# mp28164-buck-boost-flashlight-driver-tes.net
KiCad netlist of a schematic drawn in EAGLE
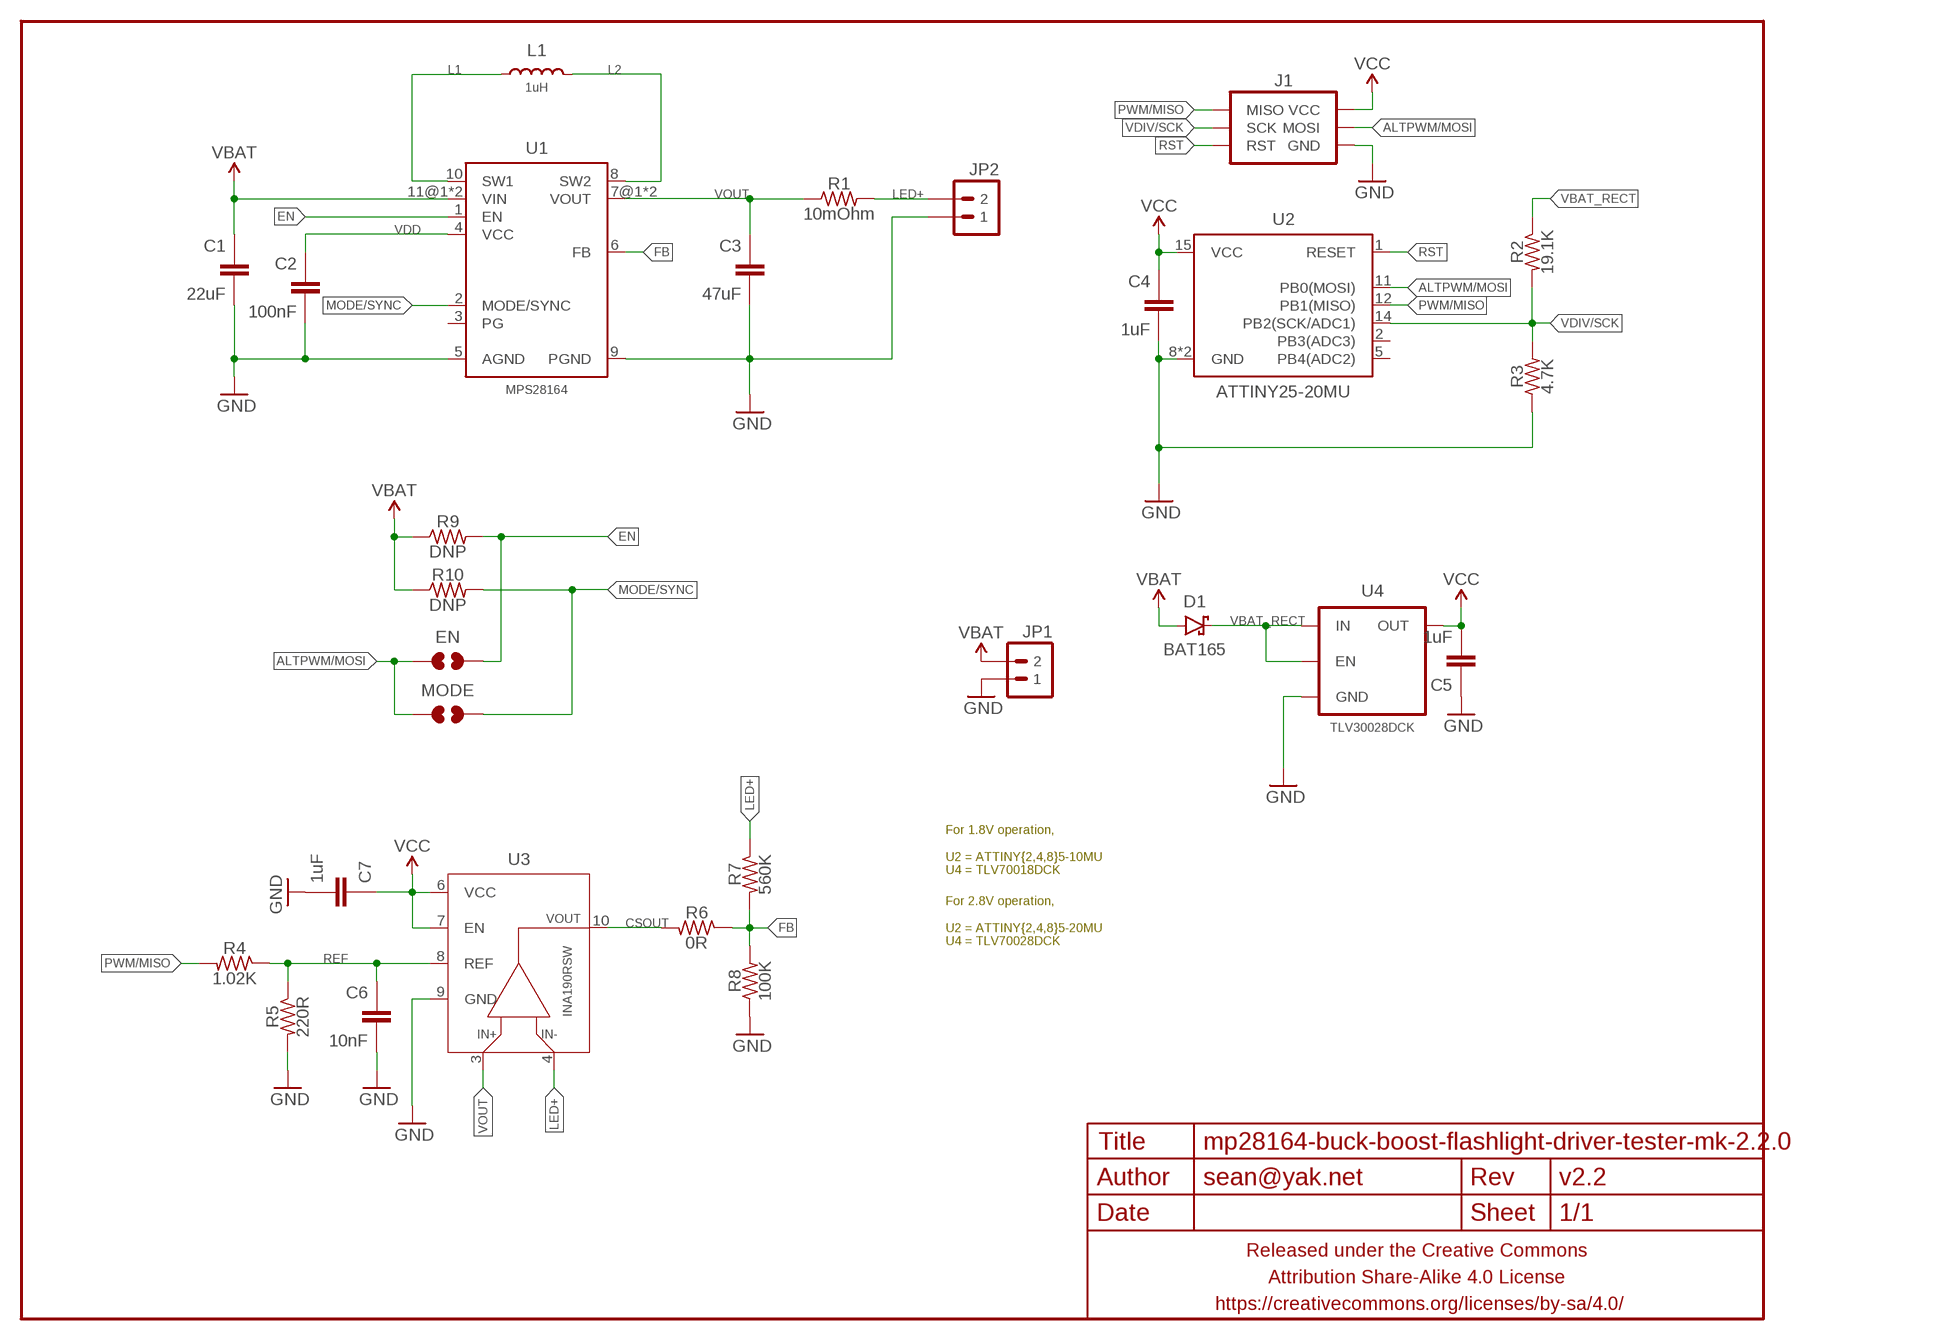
[diagram p0: schematic, sheet 1]

(export (version "E")
  (design (tool "Eeschema 10.0.6"))
  (components
    (comp (ref "C1")
      (value "22uF")
      (footprint "eagle-import:C1206")
      (libsource (lib "eagle-import") (part "CAPACITOR-CERAMICC1206"))
    )
    (comp (ref "C2")
      (value "100nF")
      (footprint "eagle-import:C0402")
      (libsource (lib "eagle-import") (part "CAPACITOR-CERAMICC0402"))
    )
    (comp (ref "C3")
      (value "47uF")
      (footprint "eagle-import:C1206")
      (libsource (lib "eagle-import") (part "CAPACITOR-CERAMICC1206"))
    )
    (comp (ref "C4")
      (value "1uF")
      (footprint "eagle-import:C0402")
      (libsource (lib "eagle-import") (part "CAPACITOR-CERAMICC0402"))
    )
    (comp (ref "C5")
      (value "1uF")
      (footprint "eagle-import:C0402")
      (libsource (lib "eagle-import") (part "CAPACITOR-CERAMICC0402"))
    )
    (comp (ref "C6")
      (value "10nF")
      (footprint "eagle-import:C0402")
      (libsource (lib "eagle-import") (part "CAPACITOR-CERAMICC0402"))
    )
    (comp (ref "C7")
      (value "1uF")
      (footprint "eagle-import:C0402")
      (libsource (lib "eagle-import") (part "CAPACITOR-CERAMICC0402"))
    )
    (comp (ref "D1")
      (value "BAT165")
      (footprint "eagle-import:SOD323-SCHOTTKY")
      (libsource (lib "eagle-import") (part "DIODE-SCHOTTKYSOD323"))
    )
    (comp (ref "EN")
      (value "JUMPER-PAD-2-NOYES_SILK")
      (footprint "eagle-import:PAD-JUMPER-2-NO_YES_SILK")
      (libsource (lib "eagle-import") (part "JUMPER-PAD-2-NOYES_SILK"))
    )
    (comp (ref "FRAME1")
      (value "FRAME-LETTERNO_PACKAGE")
      (footprint "eagle-import:DUMMY")
      (fields
        (field (name "DESIGNER") "sean@yak.net")
        (field (name "VERSION") "v2.2")
        (field (name "DESIGNER_1") "sean@yak.net")
        (field (name "VERSION_1") "v2.2")
      )
      (libsource (lib "eagle-import") (part "FRAME-LETTERNO_PACKAGE"))
    )
    (comp (ref "J1")
      (value "AVR_SPI_PRG_6PTH")
      (footprint "eagle-import:2X3")
      (libsource (lib "eagle-import") (part "AVR_SPI_PRG_6PTH"))
    )
    (comp (ref "JP1")
      (value "M021X02_NO_SILK")
      (footprint "eagle-import:1X02_NO_SILK")
      (libsource (lib "eagle-import") (part "M021X02_NO_SILK"))
    )
    (comp (ref "JP2")
      (value "M021X02_NO_SILK")
      (footprint "eagle-import:1X02_NO_SILK")
      (libsource (lib "eagle-import") (part "M021X02_NO_SILK"))
    )
    (comp (ref "L1")
      (value "1uH")
      (footprint "eagle-import:XAL60XX")
      (libsource (lib "eagle-import") (part "INDUCTORXAL60XX"))
    )
    (comp (ref "MODE")
      (value "JUMPER-PAD-2-NOYES_SILK")
      (footprint "eagle-import:PAD-JUMPER-2-NO_YES_SILK")
      (libsource (lib "eagle-import") (part "JUMPER-PAD-2-NOYES_SILK"))
    )
    (comp (ref "R1")
      (value "10mOhm")
      (footprint "eagle-import:R1206")
      (libsource (lib "eagle-import") (part "RESISTORR1206"))
    )
    (comp (ref "R2")
      (value "19.1K")
      (footprint "eagle-import:R0402")
      (libsource (lib "eagle-import") (part "RESISTORR0402"))
    )
    (comp (ref "R3")
      (value "4.7K")
      (footprint "eagle-import:R0402")
      (libsource (lib "eagle-import") (part "RESISTORR0402"))
    )
    (comp (ref "R4")
      (value "1.02K")
      (footprint "eagle-import:R0402")
      (libsource (lib "eagle-import") (part "RESISTORR0402"))
    )
    (comp (ref "R5")
      (value "220R")
      (footprint "eagle-import:R0402")
      (libsource (lib "eagle-import") (part "RESISTORR0402"))
    )
    (comp (ref "R6")
      (value "0R")
      (footprint "eagle-import:R0402")
      (libsource (lib "eagle-import") (part "RESISTORR0402"))
    )
    (comp (ref "R7")
      (value "560K")
      (footprint "eagle-import:R0402")
      (libsource (lib "eagle-import") (part "RESISTORR0402"))
    )
    (comp (ref "R8")
      (value "100K")
      (footprint "eagle-import:R0402")
      (libsource (lib "eagle-import") (part "RESISTORR0402"))
    )
    (comp (ref "R9")
      (value "DNP")
      (footprint "eagle-import:R0402")
      (libsource (lib "eagle-import") (part "RESISTORR0402"))
    )
    (comp (ref "R10")
      (value "DNP")
      (footprint "eagle-import:R0402")
      (libsource (lib "eagle-import") (part "RESISTORR0402"))
    )
    (comp (ref "U1")
      (value "MPS28164")
      (footprint "eagle-import:MPS28164")
      (libsource (lib "eagle-import") (part "MPS28164"))
    )
    (comp (ref "U2")
      (value "ATTINY25-20MU")
      (footprint "eagle-import:QFN20")
      (libsource (lib "eagle-import") (part "ATTINY45TINY85-20-QFN"))
    )
    (comp (ref "U3")
      (value "INA190RSW")
      (footprint "eagle-import:UQFN-10")
      (libsource (lib "eagle-import") (part "INA190RSW"))
    )
    (comp (ref "U4")
      (value "TLV30028DCK")
      (footprint "eagle-import:SC70-TIGHTER")
      (libsource (lib "eagle-import") (part "V_REG_ENTLV700XXDCK-TIGHTER"))
    )
  )
  (nets
    (net (code "1") (name "/CSOUT") (class "Default")
      (node (ref "R6") (pin "2") (pinfunction "2_2") (pintype "passive"))
      (node (ref "U3") (pin "10") (pinfunction "OUT_10") (pintype "bidirectional"))
    )
    (net (code "2") (name "/L1") (class "Default")
      (node (ref "L1") (pin "P$1") (pinfunction "1_P$1") (pintype "passive"))
      (node (ref "U1") (pin "10") (pinfunction "SW1_10") (pintype "bidirectional"))
    )
    (net (code "3") (name "/L2") (class "Default")
      (node (ref "L1") (pin "P$2") (pinfunction "2_P$2") (pintype "passive"))
      (node (ref "U1") (pin "8") (pinfunction "SW2_8") (pintype "bidirectional"))
    )
    (net (code "4") (name "/REF") (class "Default")
      (node (ref "C6") (pin "1") (pinfunction "1_1") (pintype "passive"))
      (node (ref "R4") (pin "1") (pinfunction "1_1") (pintype "passive"))
      (node (ref "R5") (pin "1") (pinfunction "1_1") (pintype "passive"))
      (node (ref "U3") (pin "8") (pinfunction "REF_8") (pintype "bidirectional"))
    )
    (net (code "5") (name "/VDD") (class "Default")
      (node (ref "C2") (pin "1") (pinfunction "1_1") (pintype "passive"))
      (node (ref "U1") (pin "4") (pinfunction "VCC_4") (pintype "bidirectional"))
    )
    (net (code "6") (name "ALTPWM{slash}MOSI") (class "Default")
      (node (ref "EN") (pin "1") (pinfunction "1_1") (pintype "passive"))
      (node (ref "J1") (pin "4") (pinfunction "MOSI_4") (pintype "passive"))
      (node (ref "MODE") (pin "1") (pinfunction "1_1") (pintype "passive"))
      (node (ref "U2") (pin "11") (pinfunction "PB0(MOSI)_11") (pintype "bidirectional"))
    )
    (net (code "7") (name "EN") (class "Default")
      (node (ref "EN") (pin "2") (pinfunction "2_2") (pintype "passive"))
      (node (ref "R9") (pin "2") (pinfunction "2_2") (pintype "passive"))
      (node (ref "U1") (pin "1") (pinfunction "EN_1") (pintype "bidirectional"))
    )
    (net (code "8") (name "FB") (class "Default")
      (node (ref "R6") (pin "1") (pinfunction "1_1") (pintype "passive"))
      (node (ref "R7") (pin "2") (pinfunction "2_2") (pintype "passive"))
      (node (ref "R8") (pin "2") (pinfunction "2_2") (pintype "passive"))
      (node (ref "U1") (pin "6") (pinfunction "FB_6") (pintype "bidirectional"))
    )
    (net (code "9") (name "GND") (class "Default")
      (node (ref "C1") (pin "2") (pinfunction "2_2") (pintype "passive"))
      (node (ref "C2") (pin "2") (pinfunction "2_2") (pintype "passive"))
      (node (ref "C3") (pin "2") (pinfunction "2_2") (pintype "passive"))
      (node (ref "C4") (pin "2") (pinfunction "2_2") (pintype "passive"))
      (node (ref "C5") (pin "1") (pinfunction "1_1") (pintype "passive"))
      (node (ref "C6") (pin "2") (pinfunction "2_2") (pintype "passive"))
      (node (ref "C7") (pin "2") (pinfunction "2_2") (pintype "passive"))
      (node (ref "J1") (pin "6") (pinfunction "GND_6") (pintype "passive"))
      (node (ref "JP1") (pin "1") (pinfunction "1_1") (pintype "passive"))
      (node (ref "JP2") (pin "1") (pinfunction "1_1") (pintype "passive"))
      (node (ref "R3") (pin "1") (pinfunction "1_1") (pintype "passive"))
      (node (ref "R5") (pin "2") (pinfunction "2_2") (pintype "passive"))
      (node (ref "R8") (pin "1") (pinfunction "1_1") (pintype "passive"))
      (node (ref "U1") (pin "5") (pinfunction "AGND_5") (pintype "bidirectional"))
      (node (ref "U1") (pin "9") (pinfunction "PGND_9") (pintype "bidirectional"))
      (node (ref "U2") (pin "8") (pinfunction "GND_8") (pintype "bidirectional"))
      (node (ref "U2") (pin "PAD") (pinfunction "GND_PAD") (pintype "bidirectional"))
      (node (ref "U3") (pin "9") (pinfunction "GND_9") (pintype "bidirectional"))
      (node (ref "U4") (pin "2") (pinfunction "GND_2") (pintype "input"))
    )
    (net (code "10") (name "LED+") (class "Default")
      (node (ref "JP2") (pin "2") (pinfunction "2_2") (pintype "passive"))
      (node (ref "R1") (pin "2") (pinfunction "2_2") (pintype "passive"))
      (node (ref "R7") (pin "1") (pinfunction "1_1") (pintype "passive"))
      (node (ref "U3") (pin "4") (pinfunction "VIN-_4") (pintype "bidirectional"))
    )
    (net (code "11") (name "MODE{slash}SYNC") (class "Default")
      (node (ref "MODE") (pin "2") (pinfunction "2_2") (pintype "passive"))
      (node (ref "R10") (pin "2") (pinfunction "2_2") (pintype "passive"))
      (node (ref "U1") (pin "2") (pinfunction "MODE/SYNC_2") (pintype "bidirectional"))
    )
    (net (code "12") (name "PWM{slash}MISO") (class "Default")
      (node (ref "J1") (pin "1") (pinfunction "MISO_1") (pintype "passive"))
      (node (ref "R4") (pin "2") (pinfunction "2_2") (pintype "passive"))
      (node (ref "U2") (pin "12") (pinfunction "PB1(MISO)_12") (pintype "bidirectional"))
    )
    (net (code "13") (name "RST") (class "Default")
      (node (ref "J1") (pin "5") (pinfunction "RST_5") (pintype "passive"))
      (node (ref "U2") (pin "1") (pinfunction "RESET_1") (pintype "bidirectional"))
    )
    (net (code "14") (name "VBAT") (class "Default")
      (node (ref "C1") (pin "1") (pinfunction "1_1") (pintype "passive"))
      (node (ref "D1") (pin "A") (pinfunction "A_A") (pintype "passive"))
      (node (ref "JP1") (pin "2") (pinfunction "2_2") (pintype "passive"))
      (node (ref "R10") (pin "1") (pinfunction "1_1") (pintype "passive"))
      (node (ref "R9") (pin "1") (pinfunction "1_1") (pintype "passive"))
      (node (ref "U1") (pin "11@1") (pinfunction "VIN_11@1") (pintype "bidirectional"))
      (node (ref "U1") (pin "11@2") (pinfunction "VIN_11@2") (pintype "bidirectional"))
    )
    (net (code "15") (name "VBAT_RECT") (class "Default")
      (node (ref "D1") (pin "C") (pinfunction "C_C") (pintype "passive"))
      (node (ref "R2") (pin "1") (pinfunction "1_1") (pintype "passive"))
      (node (ref "U4") (pin "1") (pinfunction "IN_1") (pintype "input"))
      (node (ref "U4") (pin "3") (pinfunction "EN_3") (pintype "input"))
    )
    (net (code "16") (name "VCC") (class "Default")
      (node (ref "C4") (pin "1") (pinfunction "1_1") (pintype "passive"))
      (node (ref "C5") (pin "2") (pinfunction "2_2") (pintype "passive"))
      (node (ref "C7") (pin "1") (pinfunction "1_1") (pintype "passive"))
      (node (ref "J1") (pin "2") (pinfunction "VCC_2") (pintype "passive"))
      (node (ref "U2") (pin "15") (pinfunction "VCC_15") (pintype "bidirectional"))
      (node (ref "U3") (pin "6") (pinfunction "VCC_6") (pintype "bidirectional"))
      (node (ref "U3") (pin "7") (pinfunction "EN_7") (pintype "bidirectional"))
      (node (ref "U4") (pin "5") (pinfunction "OUT_5") (pintype "passive"))
    )
    (net (code "17") (name "VDIV{slash}SCK") (class "Default")
      (node (ref "J1") (pin "3") (pinfunction "SCK_3") (pintype "passive"))
      (node (ref "R2") (pin "2") (pinfunction "2_2") (pintype "passive"))
      (node (ref "R3") (pin "2") (pinfunction "2_2") (pintype "passive"))
      (node (ref "U2") (pin "14") (pinfunction "PB2(SCK/ADC1)_14") (pintype "bidirectional"))
    )
    (net (code "18") (name "VOUT") (class "Default")
      (node (ref "C3") (pin "1") (pinfunction "1_1") (pintype "passive"))
      (node (ref "R1") (pin "1") (pinfunction "1_1") (pintype "passive"))
      (node (ref "U1") (pin "7@1") (pinfunction "VOUT_7@1") (pintype "bidirectional"))
      (node (ref "U1") (pin "7@2") (pinfunction "VOUT_7@2") (pintype "bidirectional"))
      (node (ref "U3") (pin "3") (pinfunction "VIN+_3") (pintype "bidirectional"))
    )
    (net (code "19") (name "unconnected-(U1-PG-Pad3)") (class "Default")
      (node (ref "U1") (pin "3") (pinfunction "PG_3") (pintype "bidirectional"))
    )
    (net (code "20") (name "unconnected-(U2-PB3(ADC3)-Pad2)") (class "Default")
      (node (ref "U2") (pin "2") (pinfunction "PB3(ADC3)_2") (pintype "bidirectional"))
    )
    (net (code "21") (name "unconnected-(U2-PB4(ADC2)-Pad5)") (class "Default")
      (node (ref "U2") (pin "5") (pinfunction "PB4(ADC2)_5") (pintype "bidirectional"))
    )
  )
)
